# 04-POWER.net
KiCad netlist of a schematic drawn in Altium Designer
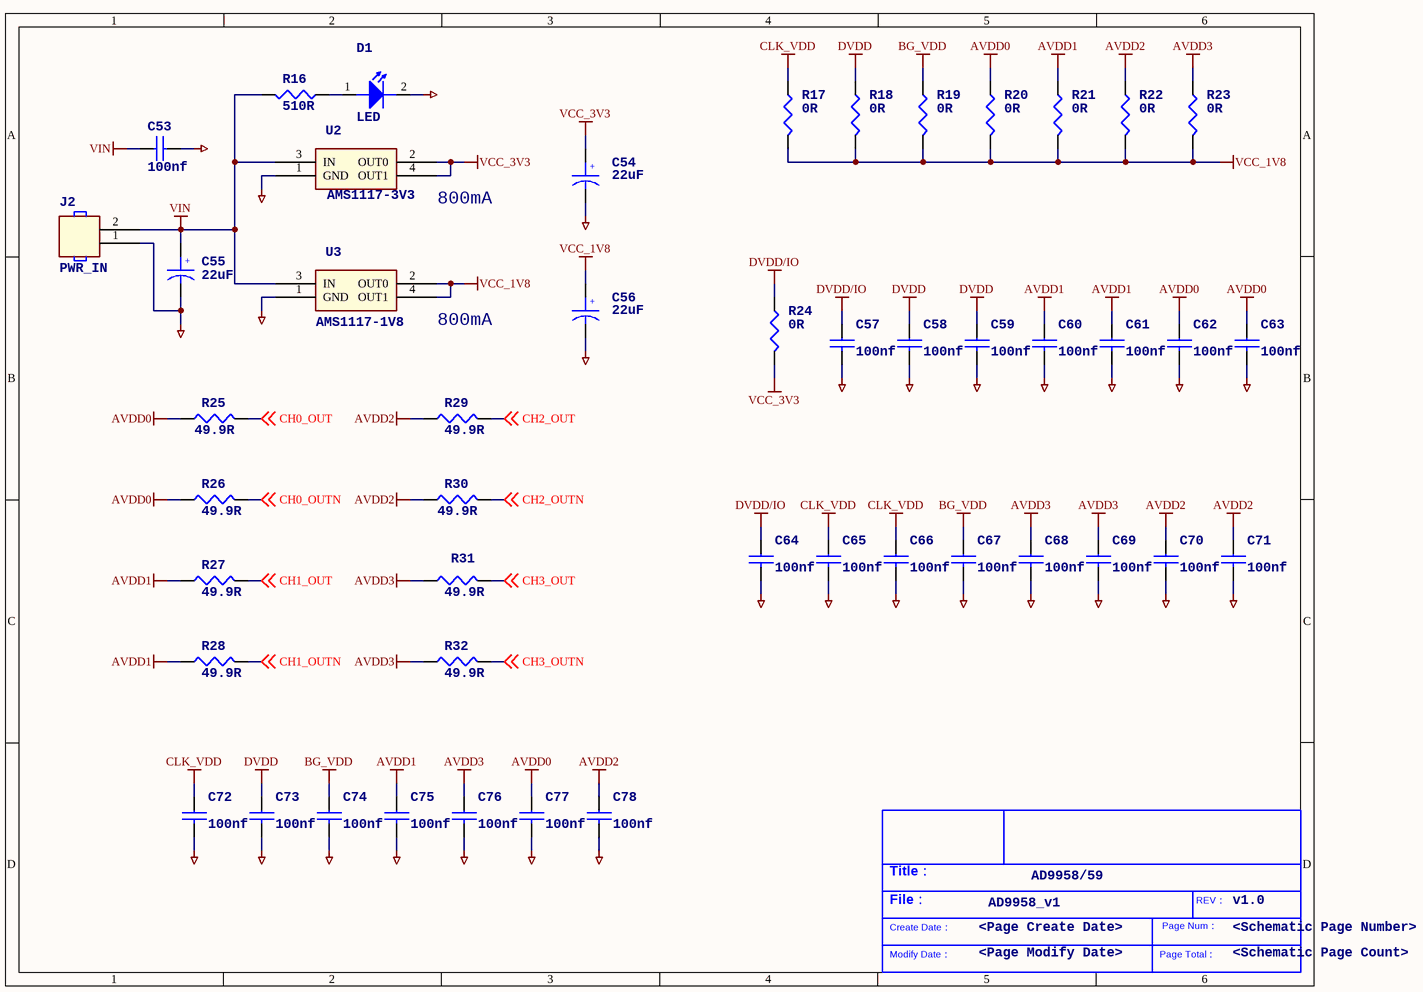
[diagram p0: 04-POWER.SchDoc]

(export (version "E")
  (design (tool "Eeschema 10.0.6"))
  (components
    (comp (ref "C53") (value "100nf") (footprint "0603C") (libsource (lib "*") (part "CAP NP")))
    (comp (ref "C54") (value "22uF") (footprint "1206T") (libsource (lib "*") (part "CAP POL")))
    (comp (ref "C55") (value "22uF") (footprint "1206T") (libsource (lib "*") (part "CAP POL")))
    (comp (ref "C56") (value "22uF") (footprint "1206T") (libsource (lib "*") (part "CAP POL")))
    (comp (ref "C57") (value "100nf") (footprint "0603C") (libsource (lib "*") (part "CAP NP")))
    (comp (ref "C58") (value "100nf") (footprint "0603C") (libsource (lib "*") (part "CAP NP")))
    (comp (ref "C59") (value "100nf") (footprint "0603C") (libsource (lib "*") (part "CAP NP")))
    (comp (ref "C60") (value "100nf") (footprint "0603C") (libsource (lib "*") (part "CAP NP")))
    (comp (ref "C61") (value "100nf") (footprint "0603C") (libsource (lib "*") (part "CAP NP")))
    (comp (ref "C62") (value "100nf") (footprint "0603C") (libsource (lib "*") (part "CAP NP")))
    (comp (ref "C63") (value "100nf") (footprint "0603C") (libsource (lib "*") (part "CAP NP")))
    (comp (ref "C64") (value "100nf") (footprint "0603C") (libsource (lib "*") (part "CAP NP")))
    (comp (ref "C65") (value "100nf") (footprint "0603C") (libsource (lib "*") (part "CAP NP")))
    (comp (ref "C66") (value "100nf") (footprint "0603C") (libsource (lib "*") (part "CAP NP")))
    (comp (ref "C67") (value "100nf") (footprint "0603C") (libsource (lib "*") (part "CAP NP")))
    (comp (ref "C68") (value "100nf") (footprint "0603C") (libsource (lib "*") (part "CAP NP")))
    (comp (ref "C69") (value "100nf") (footprint "0603C") (libsource (lib "*") (part "CAP NP")))
    (comp (ref "C70") (value "100nf") (footprint "0603C") (libsource (lib "*") (part "CAP NP")))
    (comp (ref "C71") (value "100nf") (footprint "0603C") (libsource (lib "*") (part "CAP NP")))
    (comp (ref "C72") (value "100nf") (footprint "0603C") (libsource (lib "*") (part "CAP NP")))
    (comp (ref "C73") (value "100nf") (footprint "0603C") (libsource (lib "*") (part "CAP NP")))
    (comp (ref "C74") (value "100nf") (footprint "0603C") (libsource (lib "*") (part "CAP NP")))
    (comp (ref "C75") (value "100nf") (footprint "0603C") (libsource (lib "*") (part "CAP NP")))
    (comp (ref "C76") (value "100nf") (footprint "0603C") (libsource (lib "*") (part "CAP NP")))
    (comp (ref "C77") (value "100nf") (footprint "0603C") (libsource (lib "*") (part "CAP NP")))
    (comp (ref "C78") (value "100nf") (footprint "0603C") (libsource (lib "*") (part "CAP NP")))
    (comp (ref "D1") (value "LED") (footprint "0603D") (libsource (lib "*") (part "LED")))
    (comp (ref "J2") (value "PWR_IN") (footprint "KF2EDG_3R81_2P") (libsource (lib "*") (part "HEADER 2")))
    (comp (ref "R16") (value "510R") (footprint "0603R") (libsource (lib "*") (part "R")))
    (comp (ref "R17") (value "0R") (footprint "0603R") (libsource (lib "*") (part "R")))
    (comp (ref "R18") (value "0R") (footprint "0603R") (libsource (lib "*") (part "R")))
    (comp (ref "R19") (value "0R") (footprint "0603R") (libsource (lib "*") (part "R")))
    (comp (ref "R20") (value "0R") (footprint "0603R") (libsource (lib "*") (part "R")))
    (comp (ref "R21") (value "0R") (footprint "0603R") (libsource (lib "*") (part "R")))
    (comp (ref "R22") (value "0R") (footprint "0603R") (libsource (lib "*") (part "R")))
    (comp (ref "R23") (value "0R") (footprint "0603R") (libsource (lib "*") (part "R")))
    (comp (ref "R24") (value "0R") (footprint "0603R") (libsource (lib "*") (part "R")))
    (comp (ref "R25") (value "49.9R") (footprint "0603R") (libsource (lib "*") (part "R")))
    (comp (ref "R26") (value "49.9R") (footprint "0603R") (libsource (lib "*") (part "R")))
    (comp (ref "R27") (value "49.9R") (footprint "0603R") (libsource (lib "*") (part "R")))
    (comp (ref "R28") (value "49.9R") (footprint "0603R") (libsource (lib "*") (part "R")))
    (comp (ref "R29") (value "49.9R") (footprint "0603R") (libsource (lib "*") (part "R")))
    (comp (ref "R30") (value "49.9R") (footprint "0603R") (libsource (lib "*") (part "R")))
    (comp (ref "R31") (value "49.9R") (footprint "0603R") (libsource (lib "*") (part "R")))
    (comp (ref "R32") (value "49.9R") (footprint "0603R") (libsource (lib "*") (part "R")))
    (comp (ref "U2") (value "AMS1117-3V3") (footprint "SOT223") (libsource (lib "*") (part "AMS1117-3V3")))
    (comp (ref "U3") (value "AMS1117-1V8") (footprint "SOT223") (libsource (lib "*") (part "AMS1117-3V3")))
  )
  (nets
    (net (code "1") (name "AGND") (class "Default")
      (node (ref "C53") (pin "2") (pinfunction "2_2") (pintype "passive"))
      (node (ref "C54") (pin "2") (pinfunction "2_2") (pintype "passive"))
      (node (ref "C55") (pin "2") (pinfunction "2_2") (pintype "passive"))
      (node (ref "C56") (pin "2") (pinfunction "2_2") (pintype "passive"))
      (node (ref "C57") (pin "2") (pinfunction "2_2") (pintype "passive"))
      (node (ref "C58") (pin "2") (pinfunction "2_2") (pintype "passive"))
      (node (ref "C59") (pin "2") (pinfunction "2_2") (pintype "passive"))
      (node (ref "C60") (pin "2") (pinfunction "2_2") (pintype "passive"))
      (node (ref "C61") (pin "2") (pinfunction "2_2") (pintype "passive"))
      (node (ref "C62") (pin "2") (pinfunction "2_2") (pintype "passive"))
      (node (ref "C63") (pin "2") (pinfunction "2_2") (pintype "passive"))
      (node (ref "C64") (pin "2") (pinfunction "2_2") (pintype "passive"))
      (node (ref "C65") (pin "2") (pinfunction "2_2") (pintype "passive"))
      (node (ref "C66") (pin "2") (pinfunction "2_2") (pintype "passive"))
      (node (ref "C67") (pin "2") (pinfunction "2_2") (pintype "passive"))
      (node (ref "C68") (pin "2") (pinfunction "2_2") (pintype "passive"))
      (node (ref "C69") (pin "2") (pinfunction "2_2") (pintype "passive"))
      (node (ref "C70") (pin "2") (pinfunction "2_2") (pintype "passive"))
      (node (ref "C71") (pin "2") (pinfunction "2_2") (pintype "passive"))
      (node (ref "C72") (pin "2") (pinfunction "2_2") (pintype "passive"))
      (node (ref "C73") (pin "2") (pinfunction "2_2") (pintype "passive"))
      (node (ref "C74") (pin "2") (pinfunction "2_2") (pintype "passive"))
      (node (ref "C75") (pin "2") (pinfunction "2_2") (pintype "passive"))
      (node (ref "C76") (pin "2") (pinfunction "2_2") (pintype "passive"))
      (node (ref "C77") (pin "2") (pinfunction "2_2") (pintype "passive"))
      (node (ref "C78") (pin "2") (pinfunction "2_2") (pintype "passive"))
      (node (ref "D1") (pin "2") (pinfunction "K_2") (pintype "passive"))
      (node (ref "J2") (pin "1") (pinfunction "1_1") (pintype "passive"))
      (node (ref "U2") (pin "1") (pinfunction "GND_1") (pintype "power_in"))
      (node (ref "U3") (pin "1") (pinfunction "GND_1") (pintype "power_in"))
    )
    (net (code "2") (name "AVDD0") (class "Default")
      (node (ref "C62") (pin "1") (pinfunction "1_1") (pintype "passive"))
      (node (ref "C63") (pin "1") (pinfunction "1_1") (pintype "passive"))
      (node (ref "C77") (pin "1") (pinfunction "1_1") (pintype "passive"))
      (node (ref "R20") (pin "1") (pinfunction "1_1") (pintype "passive"))
      (node (ref "R25") (pin "1") (pinfunction "1_1") (pintype "passive"))
      (node (ref "R26") (pin "1") (pinfunction "1_1") (pintype "passive"))
    )
    (net (code "3") (name "AVDD1") (class "Default")
      (node (ref "C60") (pin "1") (pinfunction "1_1") (pintype "passive"))
      (node (ref "C61") (pin "1") (pinfunction "1_1") (pintype "passive"))
      (node (ref "C75") (pin "1") (pinfunction "1_1") (pintype "passive"))
      (node (ref "R21") (pin "1") (pinfunction "1_1") (pintype "passive"))
      (node (ref "R27") (pin "1") (pinfunction "1_1") (pintype "passive"))
      (node (ref "R28") (pin "1") (pinfunction "1_1") (pintype "passive"))
    )
    (net (code "4") (name "AVDD2") (class "Default")
      (node (ref "C70") (pin "1") (pinfunction "1_1") (pintype "passive"))
      (node (ref "C71") (pin "1") (pinfunction "1_1") (pintype "passive"))
      (node (ref "C78") (pin "1") (pinfunction "1_1") (pintype "passive"))
      (node (ref "R22") (pin "1") (pinfunction "1_1") (pintype "passive"))
      (node (ref "R29") (pin "1") (pinfunction "1_1") (pintype "passive"))
      (node (ref "R30") (pin "1") (pinfunction "1_1") (pintype "passive"))
    )
    (net (code "5") (name "AVDD3") (class "Default")
      (node (ref "C68") (pin "1") (pinfunction "1_1") (pintype "passive"))
      (node (ref "C69") (pin "1") (pinfunction "1_1") (pintype "passive"))
      (node (ref "C76") (pin "1") (pinfunction "1_1") (pintype "passive"))
      (node (ref "R23") (pin "1") (pinfunction "1_1") (pintype "passive"))
      (node (ref "R31") (pin "1") (pinfunction "1_1") (pintype "passive"))
      (node (ref "R32") (pin "1") (pinfunction "1_1") (pintype "passive"))
    )
    (net (code "6") (name "BG_VDD") (class "Default")
      (node (ref "C67") (pin "1") (pinfunction "1_1") (pintype "passive"))
      (node (ref "C74") (pin "1") (pinfunction "1_1") (pintype "passive"))
      (node (ref "R19") (pin "1") (pinfunction "1_1") (pintype "passive"))
    )
    (net (code "7") (name "CH0_OUT") (class "Default")
      (node (ref "R25") (pin "2") (pinfunction "2_2") (pintype "passive"))
    )
    (net (code "8") (name "CH0_OUTN") (class "Default")
      (node (ref "R26") (pin "2") (pinfunction "2_2") (pintype "passive"))
    )
    (net (code "9") (name "CH1_OUT") (class "Default")
      (node (ref "R27") (pin "2") (pinfunction "2_2") (pintype "passive"))
    )
    (net (code "10") (name "CH1_OUTN") (class "Default")
      (node (ref "R28") (pin "2") (pinfunction "2_2") (pintype "passive"))
    )
    (net (code "11") (name "CH2_OUT") (class "Default")
      (node (ref "R29") (pin "2") (pinfunction "2_2") (pintype "passive"))
    )
    (net (code "12") (name "CH2_OUTN") (class "Default")
      (node (ref "R30") (pin "2") (pinfunction "2_2") (pintype "passive"))
    )
    (net (code "13") (name "CH3_OUT") (class "Default")
      (node (ref "R31") (pin "2") (pinfunction "2_2") (pintype "passive"))
    )
    (net (code "14") (name "CH3_OUTN") (class "Default")
      (node (ref "R32") (pin "2") (pinfunction "2_2") (pintype "passive"))
    )
    (net (code "15") (name "CLK_VDD") (class "Default")
      (node (ref "C65") (pin "1") (pinfunction "1_1") (pintype "passive"))
      (node (ref "C66") (pin "1") (pinfunction "1_1") (pintype "passive"))
      (node (ref "C72") (pin "1") (pinfunction "1_1") (pintype "passive"))
      (node (ref "R17") (pin "1") (pinfunction "1_1") (pintype "passive"))
    )
    (net (code "16") (name "DVDD") (class "Default")
      (node (ref "C58") (pin "1") (pinfunction "1_1") (pintype "passive"))
      (node (ref "C59") (pin "1") (pinfunction "1_1") (pintype "passive"))
      (node (ref "C73") (pin "1") (pinfunction "1_1") (pintype "passive"))
      (node (ref "R18") (pin "1") (pinfunction "1_1") (pintype "passive"))
    )
    (net (code "17") (name "DVDD{slash}IO") (class "Default")
      (node (ref "C57") (pin "1") (pinfunction "1_1") (pintype "passive"))
      (node (ref "C64") (pin "1") (pinfunction "1_1") (pintype "passive"))
      (node (ref "R24") (pin "1") (pinfunction "1_1") (pintype "passive"))
    )
    (net (code "18") (name "Net-(D1-A)") (class "Default")
      (node (ref "D1") (pin "1") (pinfunction "A_1") (pintype "passive"))
      (node (ref "R16") (pin "1") (pinfunction "1_1") (pintype "passive"))
    )
    (net (code "19") (name "VCC_1V8") (class "Default")
      (node (ref "C56") (pin "1") (pinfunction "1_1") (pintype "passive"))
      (node (ref "R17") (pin "2") (pinfunction "2_2") (pintype "passive"))
      (node (ref "R18") (pin "2") (pinfunction "2_2") (pintype "passive"))
      (node (ref "R19") (pin "2") (pinfunction "2_2") (pintype "passive"))
      (node (ref "R20") (pin "2") (pinfunction "2_2") (pintype "passive"))
      (node (ref "R21") (pin "2") (pinfunction "2_2") (pintype "passive"))
      (node (ref "R22") (pin "2") (pinfunction "2_2") (pintype "passive"))
      (node (ref "R23") (pin "2") (pinfunction "2_2") (pintype "passive"))
      (node (ref "U3") (pin "2") (pinfunction "OUT0_2") (pintype "passive"))
      (node (ref "U3") (pin "4") (pinfunction "OUT1_4") (pintype "passive"))
    )
    (net (code "20") (name "VCC_3V3") (class "Default")
      (node (ref "C54") (pin "1") (pinfunction "1_1") (pintype "passive"))
      (node (ref "R24") (pin "2") (pinfunction "2_2") (pintype "passive"))
      (node (ref "U2") (pin "2") (pinfunction "OUT0_2") (pintype "passive"))
      (node (ref "U2") (pin "4") (pinfunction "OUT1_4") (pintype "passive"))
    )
    (net (code "21") (name "VIN") (class "Default")
      (node (ref "C53") (pin "1") (pinfunction "1_1") (pintype "passive"))
      (node (ref "C55") (pin "1") (pinfunction "1_1") (pintype "passive"))
      (node (ref "J2") (pin "2") (pinfunction "2_2") (pintype "passive"))
      (node (ref "R16") (pin "2") (pinfunction "2_2") (pintype "passive"))
      (node (ref "U2") (pin "3") (pinfunction "IN_3") (pintype "passive"))
      (node (ref "U3") (pin "3") (pinfunction "IN_3") (pintype "passive"))
    )
  )
)
